# batteryholder2S4P.net
KiCad netlist of a schematic drawn in EAGLE
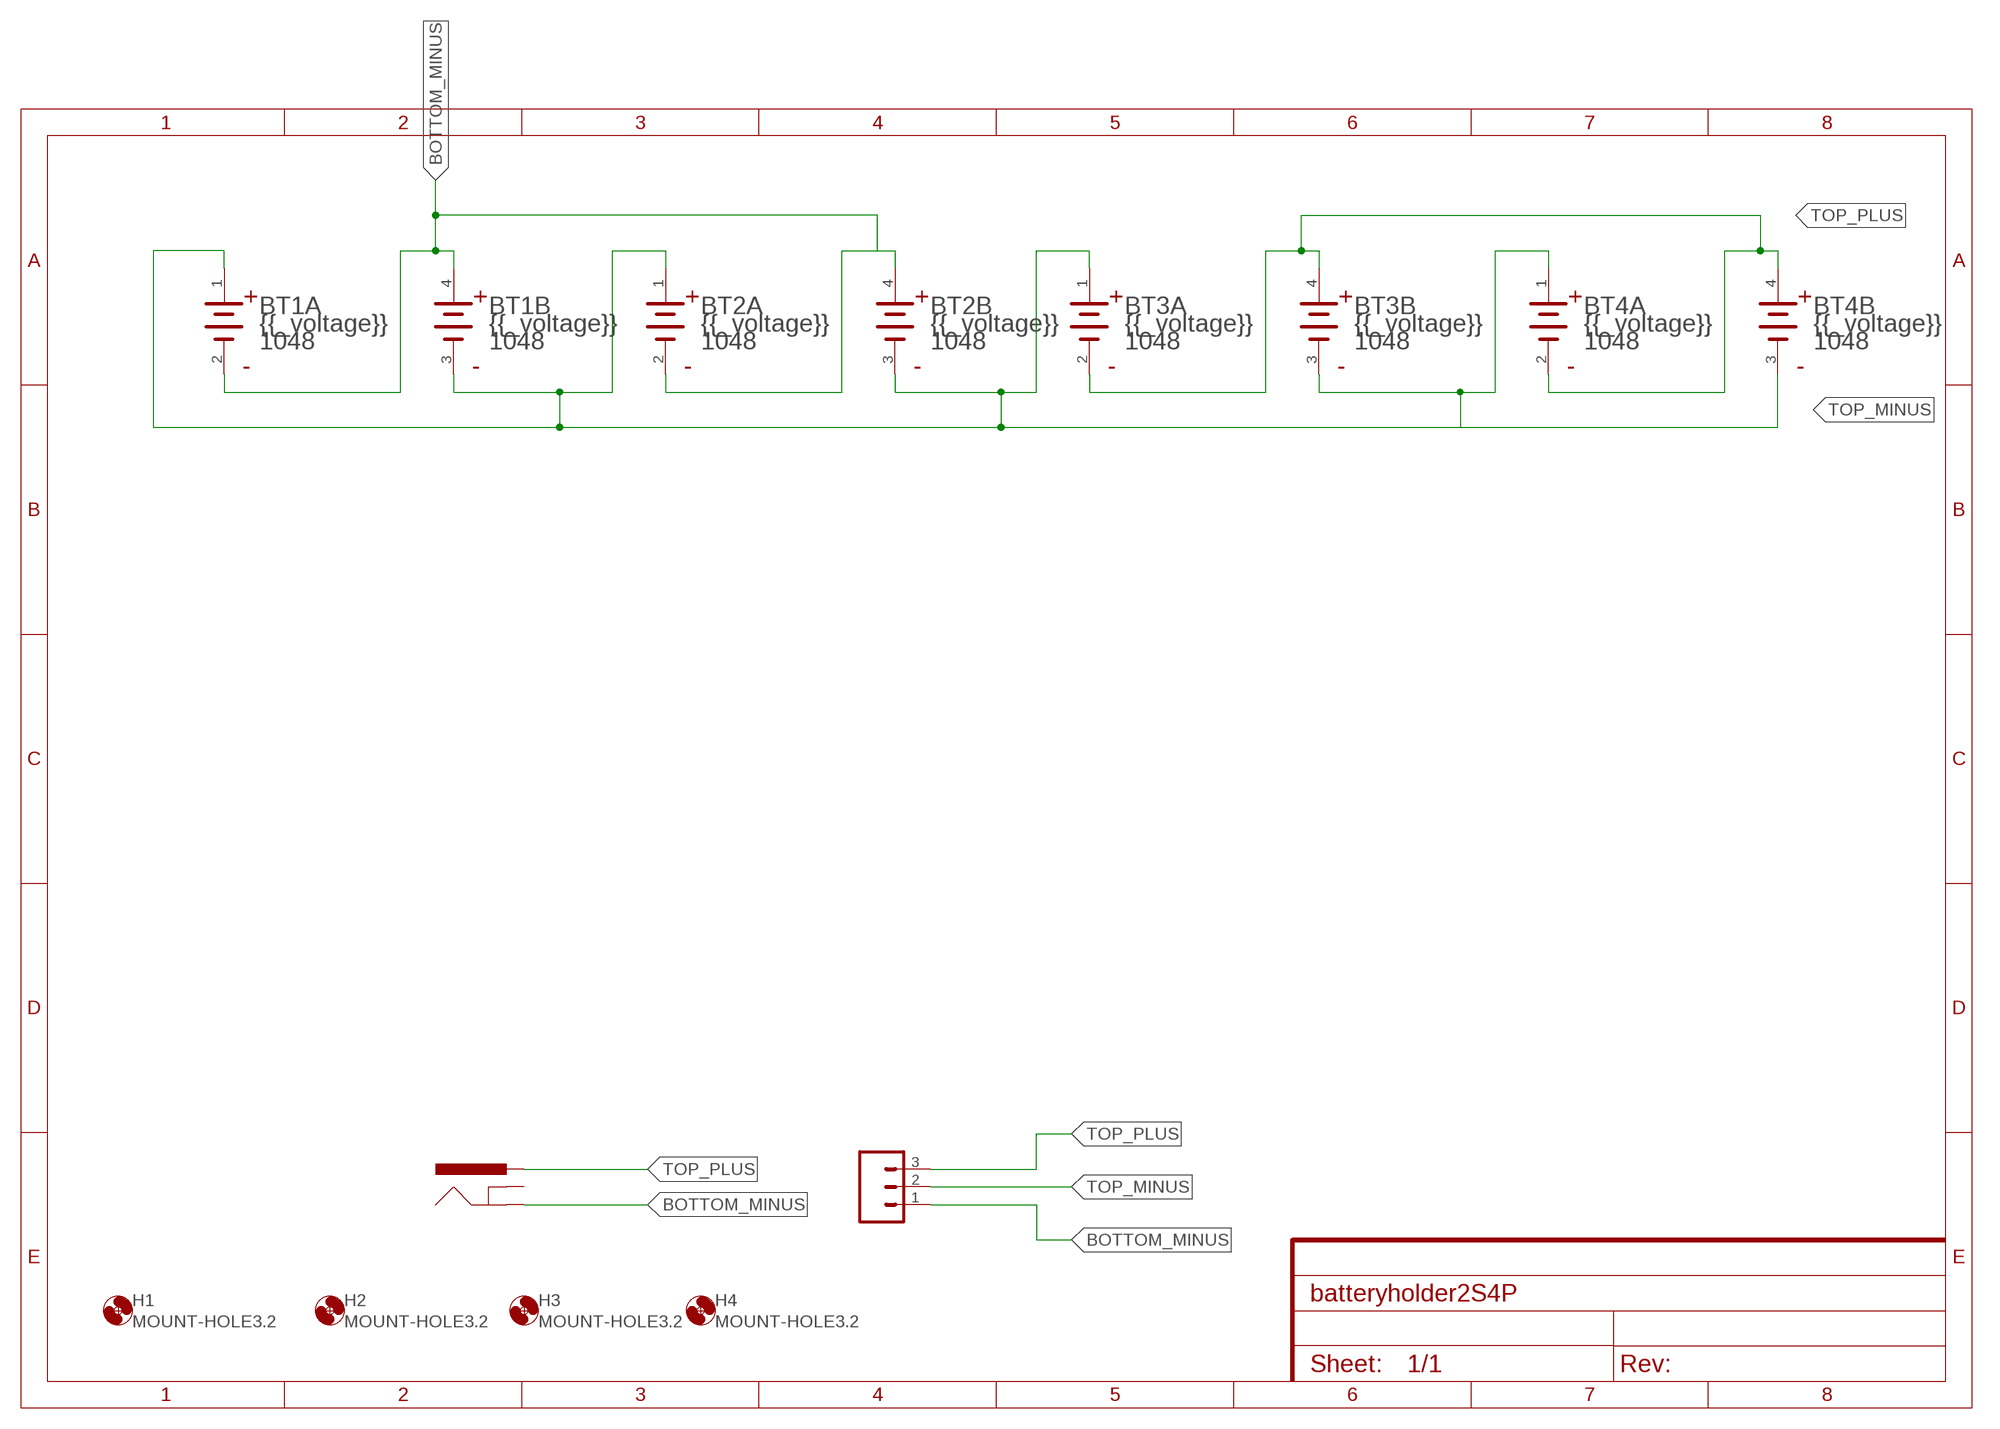
[diagram p0: schematic, sheet 1]

(export (version "E")
  (design (tool "Eeschema 10.0.6"))
  (components
    (comp (ref "BT1")
      (value "KEYSTONE_1048KEYSTONE_1048_0_0")
      (footprint "eagle-import:KEYSTONE_1048_0")
      (fields
        (field (name "DIGIKEY_PART_NUMBER") "36-1048-ND")
        (field (name "MF") "Keystone")
        (field (name "MOUSER_PART_NUMBER") "534-1048")
      )
      (libsource (lib "eagle-import") (part "KEYSTONE_1048KEYSTONE_1048_0_0"))
    )
    (comp (ref "BT2")
      (value "KEYSTONE_1048KEYSTONE_1048_0_0")
      (footprint "eagle-import:KEYSTONE_1048_0")
      (fields
        (field (name "DIGIKEY_PART_NUMBER") "36-1048-ND")
        (field (name "MF") "Keystone")
        (field (name "MOUSER_PART_NUMBER") "534-1048")
      )
      (libsource (lib "eagle-import") (part "KEYSTONE_1048KEYSTONE_1048_0_0"))
    )
    (comp (ref "BT3")
      (value "KEYSTONE_1048KEYSTONE_1048_0_0")
      (footprint "eagle-import:KEYSTONE_1048_0")
      (fields
        (field (name "DIGIKEY_PART_NUMBER") "36-1048-ND")
        (field (name "MF") "Keystone")
        (field (name "MOUSER_PART_NUMBER") "534-1048")
      )
      (libsource (lib "eagle-import") (part "KEYSTONE_1048KEYSTONE_1048_0_0"))
    )
    (comp (ref "BT4")
      (value "KEYSTONE_1048KEYSTONE_1048_0_0")
      (footprint "eagle-import:KEYSTONE_1048_0")
      (fields
        (field (name "DIGIKEY_PART_NUMBER") "36-1048-ND")
        (field (name "MF") "Keystone")
        (field (name "MOUSER_PART_NUMBER") "534-1048")
      )
      (libsource (lib "eagle-import") (part "KEYSTONE_1048KEYSTONE_1048_0_0"))
    )
    (comp (ref "H1")
      (value "MOUNT-HOLE3.2")
      (footprint "eagle-import:3,2")
      (libsource (lib "eagle-import") (part "MOUNT-HOLE3.2"))
    )
    (comp (ref "H2")
      (value "MOUNT-HOLE3.2")
      (footprint "eagle-import:3,2")
      (libsource (lib "eagle-import") (part "MOUNT-HOLE3.2"))
    )
    (comp (ref "H3")
      (value "MOUNT-HOLE3.2")
      (footprint "eagle-import:3,2")
      (libsource (lib "eagle-import") (part "MOUNT-HOLE3.2"))
    )
    (comp (ref "H4")
      (value "MOUNT-HOLE3.2")
      (footprint "eagle-import:3,2")
      (libsource (lib "eagle-import") (part "MOUNT-HOLE3.2"))
    )
    (comp (ref "J1")
      (value "CONN_03-SCREW-5MM")
      (footprint "eagle-import:SCREWTERMINAL-5MM-3")
      (libsource (lib "eagle-import") (part "CONN_03-SCREW-5MM"))
    )
    (comp (ref "J3")
      (value "POWER_JACKPTH_BREAD")
      (footprint "eagle-import:POWER_JACK_PTH_BREAD")
      (libsource (lib "eagle-import") (part "POWER_JACKPTH_BREAD"))
    )
  )
  (nets
    (net (code "1") (name "BOTTOM_MINUS") (class "Default")
      (node (ref "BT1") (pin "2") (pinfunction "1_CATHODE_2") (pintype "passive"))
      (node (ref "BT1") (pin "4") (pinfunction "2_ANODE_4") (pintype "passive"))
      (node (ref "BT2") (pin "2") (pinfunction "1_CATHODE_2") (pintype "passive"))
      (node (ref "BT2") (pin "4") (pinfunction "2_ANODE_4") (pintype "passive"))
      (node (ref "J1") (pin "1") (pinfunction "1_1") (pintype "passive"))
      (node (ref "J3") (pin "GND") (pinfunction "GND_GND") (pintype "bidirectional"))
    )
    (net (code "2") (name "TOP_MINUS") (class "Default")
      (node (ref "BT1") (pin "1") (pinfunction "1_ANODE_1") (pintype "passive"))
      (node (ref "BT1") (pin "3") (pinfunction "2_CATHODE_3") (pintype "passive"))
      (node (ref "BT2") (pin "1") (pinfunction "1_ANODE_1") (pintype "passive"))
      (node (ref "BT2") (pin "3") (pinfunction "2_CATHODE_3") (pintype "passive"))
      (node (ref "BT3") (pin "1") (pinfunction "1_ANODE_1") (pintype "passive"))
      (node (ref "BT3") (pin "3") (pinfunction "2_CATHODE_3") (pintype "passive"))
      (node (ref "BT4") (pin "1") (pinfunction "1_ANODE_1") (pintype "passive"))
      (node (ref "BT4") (pin "3") (pinfunction "2_CATHODE_3") (pintype "passive"))
      (node (ref "J1") (pin "2") (pinfunction "2_2") (pintype "passive"))
    )
    (net (code "3") (name "TOP_PLUS") (class "Default")
      (node (ref "BT3") (pin "2") (pinfunction "1_CATHODE_2") (pintype "passive"))
      (node (ref "BT3") (pin "4") (pinfunction "2_ANODE_4") (pintype "passive"))
      (node (ref "BT4") (pin "2") (pinfunction "1_CATHODE_2") (pintype "passive"))
      (node (ref "BT4") (pin "4") (pinfunction "2_ANODE_4") (pintype "passive"))
      (node (ref "J1") (pin "3") (pinfunction "3_3") (pintype "passive"))
      (node (ref "J3") (pin "PWR") (pinfunction "PWR_PWR") (pintype "bidirectional"))
    )
    (net (code "4") (name "unconnected-(J3-PadGNDBREAK)") (class "Default")
      (node (ref "J3") (pin "GNDBREAK") (pinfunction "GNDBREAK_GNDBREAK") (pintype "bidirectional"))
    )
  )
)
